# Oscilador267MHz.net
KiCad netlist of a schematic drawn in Altium Designer
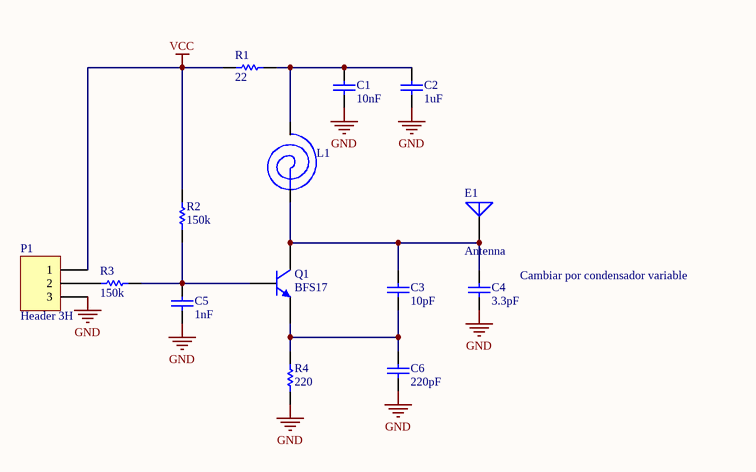
[diagram p0: Oscilador267MHz.SchDoc]

(export (version "E")
  (design (tool "Eeschema 10.0.6"))
  (components
    (comp (ref "C1")
      (value "10nF")
      (footprint "0805_CAP")
      (fields (field (name "Comment") "Capacitor"))
      (libsource (lib "epf") (part "Cap"))
    )
    (comp (ref "C2")
      (value "1uF")
      (footprint "0805_CAP")
      (fields (field (name "Comment") "Capacitor"))
      (libsource (lib "epf") (part "Cap"))
    )
    (comp (ref "C3")
      (value "10pF")
      (footprint "0805_CAP")
      (fields (field (name "Comment") "Capacitor"))
      (libsource (lib "epf") (part "Cap"))
    )
    (comp (ref "C4")
      (value "3.3pF")
      (footprint "0805_CAP")
      (fields (field (name "Comment") "Capacitor"))
      (libsource (lib "epf") (part "Cap"))
    )
    (comp (ref "C5")
      (value "1nF")
      (footprint "0805_CAP")
      (fields (field (name "Comment") "Capacitor"))
      (libsource (lib "epf") (part "Cap"))
    )
    (comp (ref "C6")
      (value "220pF")
      (footprint "0805_CAP")
      (fields (field (name "Comment") "Capacitor"))
      (libsource (lib "epf") (part "Cap"))
    )
    (comp (ref "E1")
      (value "Antenna")
      (footprint "PIN1")
      (description "Generic Antenna")
      (fields (field (name "PUBLISHER") "Altium Limited"))
      (libsource (lib "Miscellaneous Devices") (part "Antenna"))
    )
    (comp (ref "L1")
      (value "MicrostripInd")
      (footprint "MSIND_33nH")
      (description "Bobina microstrip calculadas con ADS")
      (libsource (lib "epf") (part "MSIND"))
    )
    (comp (ref "P1")
      (value "Header 3H")
      (footprint "HDR1X3H")
      (description "Header, 3-Pin, Right Angle")
      (fields (field (name "PUBLISHER") "Altium Limited"))
      (libsource (lib "Miscellaneous Connectors") (part "Header 3H"))
    )
    (comp (ref "Q1")
      (value "BFS17")
      (footprint "SOT23")
      (description "NPN 1 GHz Wideband Transistor")
      (fields (field (name "PUBLISHER") "Altium Limited"))
      (libsource (lib "epf") (part "BFS17"))
    )
    (comp (ref "R1")
      (value "22")
      (footprint "0805_RES")
      (fields (field (name "Comment") "Resistor"))
      (libsource (lib "epf") (part "Res"))
    )
    (comp (ref "R2")
      (value "150k")
      (footprint "0805_RES")
      (fields (field (name "Comment") "Resistor"))
      (libsource (lib "epf") (part "Res"))
    )
    (comp (ref "R3")
      (value "150k")
      (footprint "0805_RES")
      (fields (field (name "Comment") "Resistor"))
      (libsource (lib "epf") (part "Res"))
    )
    (comp (ref "R4")
      (value "220")
      (footprint "0805_RES")
      (fields (field (name "Comment") "Resistor"))
      (libsource (lib "epf") (part "Res"))
    )
  )
  (nets
    (net (code "1") (name "GND") (class "Default")
      (node (ref "C1") (pin "1") (pinfunction "1_1") (pintype "passive"))
      (node (ref "C2") (pin "1") (pinfunction "1_1") (pintype "passive"))
      (node (ref "C4") (pin "1") (pinfunction "1_1") (pintype "passive"))
      (node (ref "C5") (pin "1") (pinfunction "1_1") (pintype "passive"))
      (node (ref "C6") (pin "1") (pinfunction "1_1") (pintype "passive"))
      (node (ref "P1") (pin "3") (pinfunction "3_3") (pintype "passive"))
      (node (ref "R4") (pin "2") (pinfunction "2_2") (pintype "passive"))
    )
    (net (code "2") (name "Net-(C1-Pad2)") (class "Default")
      (node (ref "C1") (pin "2") (pinfunction "2_2") (pintype "passive"))
      (node (ref "C2") (pin "2") (pinfunction "2_2") (pintype "passive"))
      (node (ref "L1") (pin "1") (pinfunction "1_1") (pintype "passive"))
      (node (ref "R1") (pin "2") (pinfunction "2_2") (pintype "passive"))
    )
    (net (code "3") (name "Net-(E1-A)") (class "Default")
      (node (ref "C3") (pin "2") (pinfunction "2_2") (pintype "passive"))
      (node (ref "C4") (pin "2") (pinfunction "2_2") (pintype "passive"))
      (node (ref "E1") (pin "1") (pinfunction "A_1") (pintype "passive"))
      (node (ref "L1") (pin "2") (pinfunction "2_2") (pintype "passive"))
      (node (ref "Q1") (pin "3") (pinfunction "C_3") (pintype "passive"))
    )
    (net (code "4") (name "Net-(P1-Pad2)") (class "Default")
      (node (ref "P1") (pin "2") (pinfunction "2_2") (pintype "passive"))
      (node (ref "R3") (pin "1") (pinfunction "1_1") (pintype "passive"))
    )
    (net (code "5") (name "Net-(Q1-B)") (class "Default")
      (node (ref "C5") (pin "2") (pinfunction "2_2") (pintype "passive"))
      (node (ref "Q1") (pin "1") (pinfunction "B_1") (pintype "passive"))
      (node (ref "R2") (pin "2") (pinfunction "2_2") (pintype "passive"))
      (node (ref "R3") (pin "2") (pinfunction "2_2") (pintype "passive"))
    )
    (net (code "6") (name "Net-(Q1-E)") (class "Default")
      (node (ref "C3") (pin "1") (pinfunction "1_1") (pintype "passive"))
      (node (ref "C6") (pin "2") (pinfunction "2_2") (pintype "passive"))
      (node (ref "Q1") (pin "2") (pinfunction "E_2") (pintype "passive"))
      (node (ref "R4") (pin "1") (pinfunction "1_1") (pintype "passive"))
    )
    (net (code "7") (name "VCC") (class "Default")
      (node (ref "P1") (pin "1") (pinfunction "1_1") (pintype "passive"))
      (node (ref "R1") (pin "1") (pinfunction "1_1") (pintype "passive"))
      (node (ref "R2") (pin "1") (pinfunction "1_1") (pintype "passive"))
    )
  )
)
